# orb.net
KiCad netlist of a schematic drawn in EAGLE
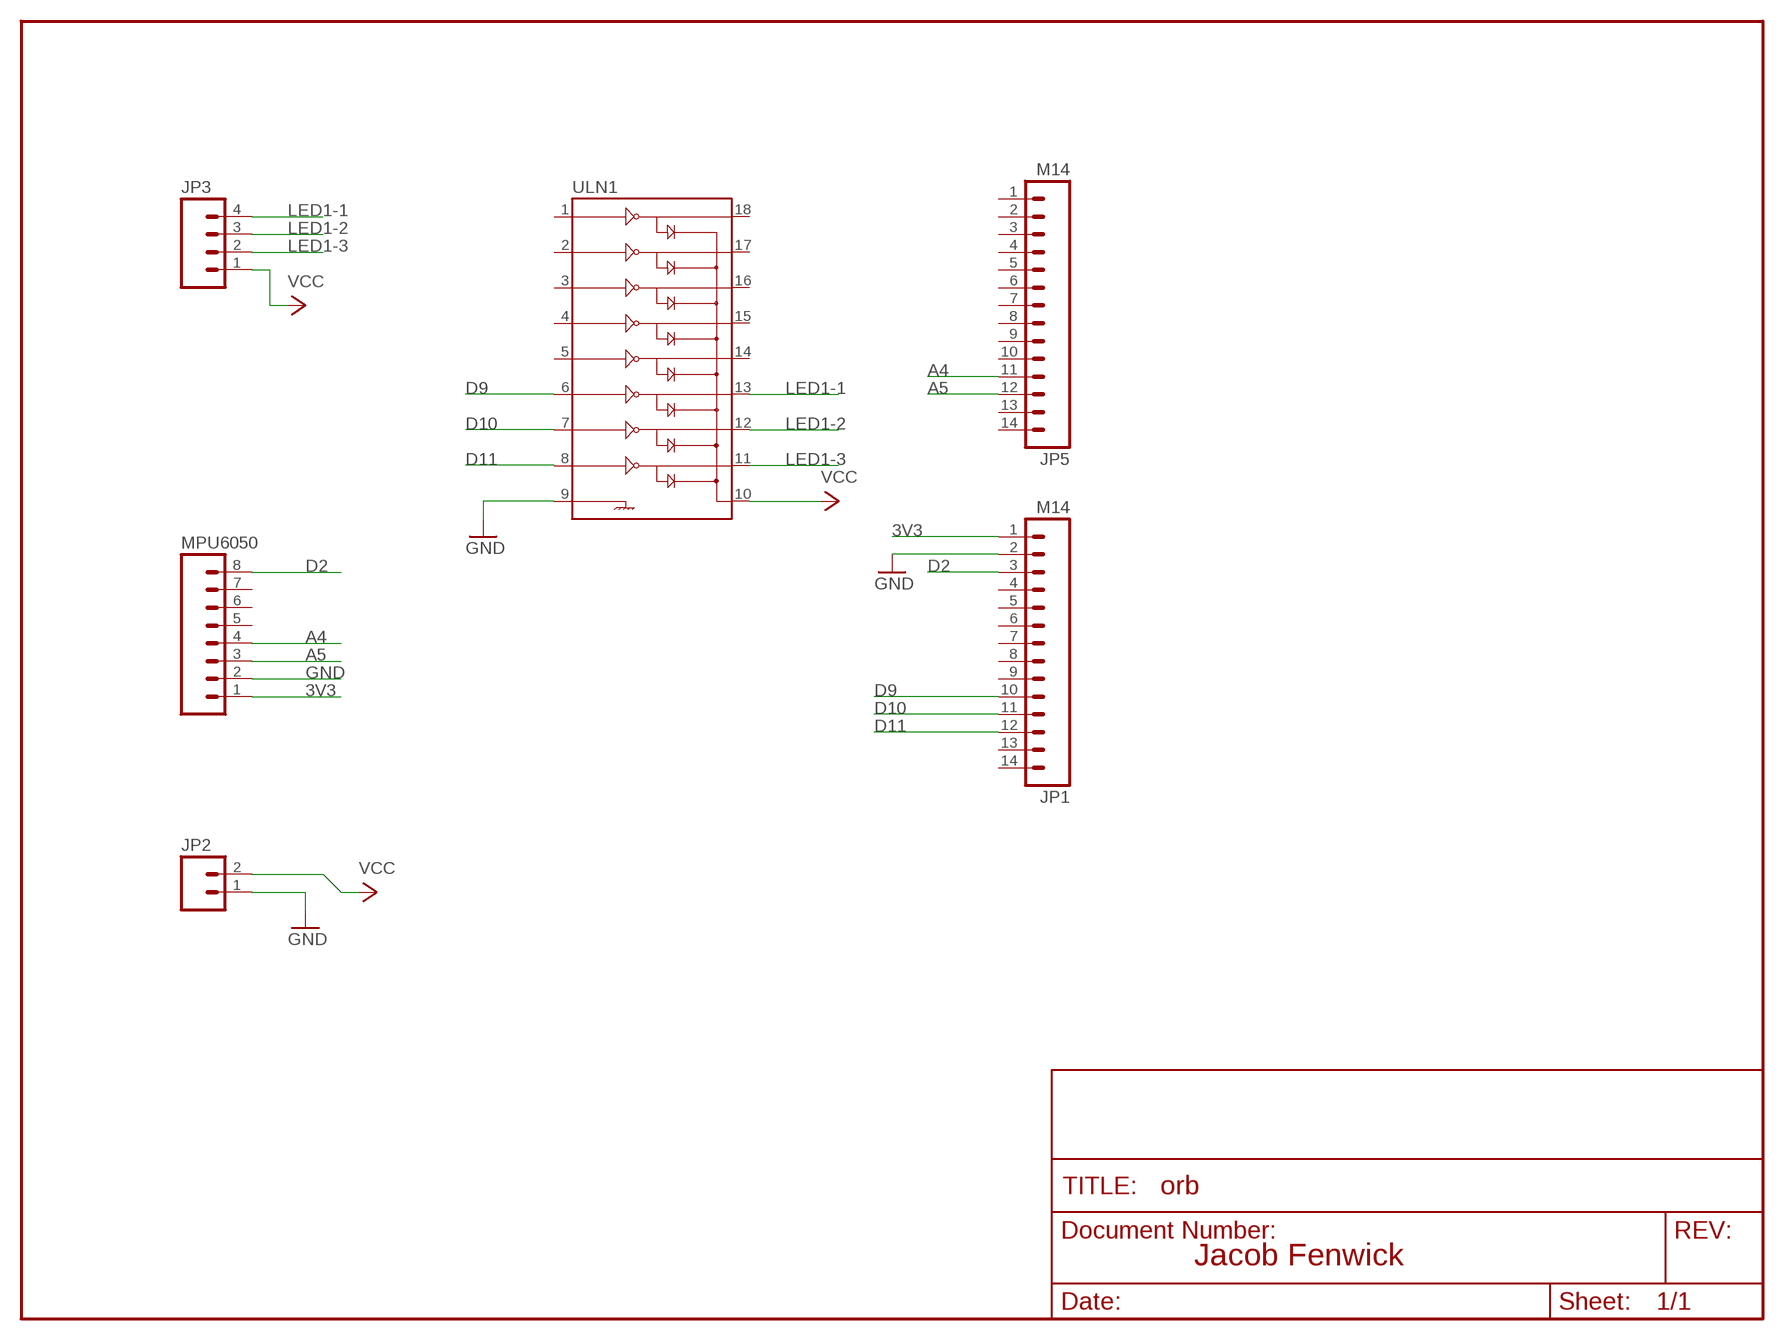
[diagram p0: schematic, sheet 1]

(export (version "E")
  (design (tool "Eeschema 10.0.6"))
  (components
    (comp (ref "JP1")
      (value "M14")
      (footprint "eagle-import:1X14")
      (libsource (lib "eagle-import") (part "M14"))
    )
    (comp (ref "JP2")
      (value "M02PTH")
      (footprint "eagle-import:1X02")
      (libsource (lib "eagle-import") (part "M02PTH"))
    )
    (comp (ref "JP3")
      (value "M04PTH")
      (footprint "eagle-import:1X04")
      (libsource (lib "eagle-import") (part "M04PTH"))
    )
    (comp (ref "JP5")
      (value "M14")
      (footprint "eagle-import:1X14")
      (libsource (lib "eagle-import") (part "M14"))
    )
    (comp (ref "MPU6050")
      (value "M081X08")
      (footprint "eagle-import:1X08")
      (libsource (lib "eagle-import") (part "M081X08"))
    )
    (comp (ref "ULN1")
      (value "ULN2803DIP")
      (footprint "eagle-import:DIL18")
      (libsource (lib "eagle-import") (part "ULN2803DIP"))
    )
  )
  (nets
    (net (code "1") (name "/3V3") (class "Default")
      (node (ref "JP1") (pin "1") (pinfunction "1_1") (pintype "passive"))
      (node (ref "MPU6050") (pin "1") (pinfunction "1_1") (pintype "passive"))
    )
    (net (code "2") (name "/A4") (class "Default")
      (node (ref "JP5") (pin "11") (pinfunction "11_11") (pintype "passive"))
      (node (ref "MPU6050") (pin "4") (pinfunction "4_4") (pintype "passive"))
    )
    (net (code "3") (name "/A5") (class "Default")
      (node (ref "JP5") (pin "12") (pinfunction "12_12") (pintype "passive"))
      (node (ref "MPU6050") (pin "3") (pinfunction "3_3") (pintype "passive"))
    )
    (net (code "4") (name "/D2") (class "Default")
      (node (ref "JP1") (pin "3") (pinfunction "3_3") (pintype "passive"))
      (node (ref "MPU6050") (pin "8") (pinfunction "8_8") (pintype "passive"))
    )
    (net (code "5") (name "/D9") (class "Default")
      (node (ref "JP1") (pin "10") (pinfunction "10_10") (pintype "passive"))
      (node (ref "ULN1") (pin "6") (pinfunction "6_6") (pintype "bidirectional"))
    )
    (net (code "6") (name "/D10") (class "Default")
      (node (ref "JP1") (pin "11") (pinfunction "11_11") (pintype "passive"))
      (node (ref "ULN1") (pin "7") (pinfunction "7_7") (pintype "bidirectional"))
    )
    (net (code "7") (name "/D11") (class "Default")
      (node (ref "JP1") (pin "12") (pinfunction "12_12") (pintype "passive"))
      (node (ref "ULN1") (pin "8") (pinfunction "8_8") (pintype "bidirectional"))
    )
    (net (code "8") (name "/LED1-1") (class "Default")
      (node (ref "JP3") (pin "4") (pinfunction "4_4") (pintype "passive"))
      (node (ref "ULN1") (pin "13") (pinfunction "13_13") (pintype "bidirectional"))
    )
    (net (code "9") (name "/LED1-2") (class "Default")
      (node (ref "JP3") (pin "3") (pinfunction "3_3") (pintype "passive"))
      (node (ref "ULN1") (pin "12") (pinfunction "12_12") (pintype "bidirectional"))
    )
    (net (code "10") (name "/LED1-3") (class "Default")
      (node (ref "JP3") (pin "2") (pinfunction "2_2") (pintype "passive"))
      (node (ref "ULN1") (pin "11") (pinfunction "11_11") (pintype "bidirectional"))
    )
    (net (code "11") (name "GND") (class "Default")
      (node (ref "JP1") (pin "2") (pinfunction "2_2") (pintype "passive"))
      (node (ref "JP2") (pin "1") (pinfunction "1_1") (pintype "passive"))
      (node (ref "MPU6050") (pin "2") (pinfunction "2_2") (pintype "passive"))
      (node (ref "ULN1") (pin "9") (pinfunction "9_9") (pintype "bidirectional"))
    )
    (net (code "12") (name "VCC") (class "Default")
      (node (ref "JP2") (pin "2") (pinfunction "2_2") (pintype "passive"))
      (node (ref "JP3") (pin "1") (pinfunction "1_1") (pintype "passive"))
      (node (ref "ULN1") (pin "10") (pinfunction "10_10") (pintype "bidirectional"))
    )
    (net (code "13") (name "unconnected-(JP1-Pad4)") (class "Default")
      (node (ref "JP1") (pin "4") (pinfunction "4_4") (pintype "passive"))
    )
    (net (code "14") (name "unconnected-(JP1-Pad5)") (class "Default")
      (node (ref "JP1") (pin "5") (pinfunction "5_5") (pintype "passive"))
    )
    (net (code "15") (name "unconnected-(JP1-Pad6)") (class "Default")
      (node (ref "JP1") (pin "6") (pinfunction "6_6") (pintype "passive"))
    )
    (net (code "16") (name "unconnected-(JP1-Pad7)") (class "Default")
      (node (ref "JP1") (pin "7") (pinfunction "7_7") (pintype "passive"))
    )
    (net (code "17") (name "unconnected-(JP1-Pad8)") (class "Default")
      (node (ref "JP1") (pin "8") (pinfunction "8_8") (pintype "passive"))
    )
    (net (code "18") (name "unconnected-(JP1-Pad9)") (class "Default")
      (node (ref "JP1") (pin "9") (pinfunction "9_9") (pintype "passive"))
    )
    (net (code "19") (name "unconnected-(JP1-Pad13)") (class "Default")
      (node (ref "JP1") (pin "13") (pinfunction "13_13") (pintype "passive"))
    )
    (net (code "20") (name "unconnected-(JP1-Pad14)") (class "Default")
      (node (ref "JP1") (pin "14") (pinfunction "14_14") (pintype "passive"))
    )
    (net (code "21") (name "unconnected-(JP5-Pad1)") (class "Default")
      (node (ref "JP5") (pin "1") (pinfunction "1_1") (pintype "passive"))
    )
    (net (code "22") (name "unconnected-(JP5-Pad2)") (class "Default")
      (node (ref "JP5") (pin "2") (pinfunction "2_2") (pintype "passive"))
    )
    (net (code "23") (name "unconnected-(JP5-Pad3)") (class "Default")
      (node (ref "JP5") (pin "3") (pinfunction "3_3") (pintype "passive"))
    )
    (net (code "24") (name "unconnected-(JP5-Pad4)") (class "Default")
      (node (ref "JP5") (pin "4") (pinfunction "4_4") (pintype "passive"))
    )
    (net (code "25") (name "unconnected-(JP5-Pad5)") (class "Default")
      (node (ref "JP5") (pin "5") (pinfunction "5_5") (pintype "passive"))
    )
    (net (code "26") (name "unconnected-(JP5-Pad6)") (class "Default")
      (node (ref "JP5") (pin "6") (pinfunction "6_6") (pintype "passive"))
    )
    (net (code "27") (name "unconnected-(JP5-Pad7)") (class "Default")
      (node (ref "JP5") (pin "7") (pinfunction "7_7") (pintype "passive"))
    )
    (net (code "28") (name "unconnected-(JP5-Pad8)") (class "Default")
      (node (ref "JP5") (pin "8") (pinfunction "8_8") (pintype "passive"))
    )
    (net (code "29") (name "unconnected-(JP5-Pad9)") (class "Default")
      (node (ref "JP5") (pin "9") (pinfunction "9_9") (pintype "passive"))
    )
    (net (code "30") (name "unconnected-(JP5-Pad10)") (class "Default")
      (node (ref "JP5") (pin "10") (pinfunction "10_10") (pintype "passive"))
    )
    (net (code "31") (name "unconnected-(JP5-Pad13)") (class "Default")
      (node (ref "JP5") (pin "13") (pinfunction "13_13") (pintype "passive"))
    )
    (net (code "32") (name "unconnected-(JP5-Pad14)") (class "Default")
      (node (ref "JP5") (pin "14") (pinfunction "14_14") (pintype "passive"))
    )
    (net (code "33") (name "unconnected-(MPU6050-Pad5)") (class "Default")
      (node (ref "MPU6050") (pin "5") (pinfunction "5_5") (pintype "passive"))
    )
    (net (code "34") (name "unconnected-(MPU6050-Pad6)") (class "Default")
      (node (ref "MPU6050") (pin "6") (pinfunction "6_6") (pintype "passive"))
    )
    (net (code "35") (name "unconnected-(MPU6050-Pad7)") (class "Default")
      (node (ref "MPU6050") (pin "7") (pinfunction "7_7") (pintype "passive"))
    )
    (net (code "36") (name "unconnected-(ULN1-Pad1)") (class "Default")
      (node (ref "ULN1") (pin "1") (pinfunction "1_1") (pintype "bidirectional"))
    )
    (net (code "37") (name "unconnected-(ULN1-Pad2)") (class "Default")
      (node (ref "ULN1") (pin "2") (pinfunction "2_2") (pintype "bidirectional"))
    )
    (net (code "38") (name "unconnected-(ULN1-Pad3)") (class "Default")
      (node (ref "ULN1") (pin "3") (pinfunction "3_3") (pintype "bidirectional"))
    )
    (net (code "39") (name "unconnected-(ULN1-Pad4)") (class "Default")
      (node (ref "ULN1") (pin "4") (pinfunction "4_4") (pintype "bidirectional"))
    )
    (net (code "40") (name "unconnected-(ULN1-Pad5)") (class "Default")
      (node (ref "ULN1") (pin "5") (pinfunction "5_5") (pintype "bidirectional"))
    )
    (net (code "41") (name "unconnected-(ULN1-Pad14)") (class "Default")
      (node (ref "ULN1") (pin "14") (pinfunction "14_14") (pintype "bidirectional"))
    )
    (net (code "42") (name "unconnected-(ULN1-Pad15)") (class "Default")
      (node (ref "ULN1") (pin "15") (pinfunction "15_15") (pintype "bidirectional"))
    )
    (net (code "43") (name "unconnected-(ULN1-Pad16)") (class "Default")
      (node (ref "ULN1") (pin "16") (pinfunction "16_16") (pintype "bidirectional"))
    )
    (net (code "44") (name "unconnected-(ULN1-Pad17)") (class "Default")
      (node (ref "ULN1") (pin "17") (pinfunction "17_17") (pintype "bidirectional"))
    )
    (net (code "45") (name "unconnected-(ULN1-Pad18)") (class "Default")
      (node (ref "ULN1") (pin "18") (pinfunction "18_18") (pintype "bidirectional"))
    )
  )
)
